# LB_BIT_o2_LONGLED-v02_rev1.net
KiCad netlist of a schematic drawn in EAGLE
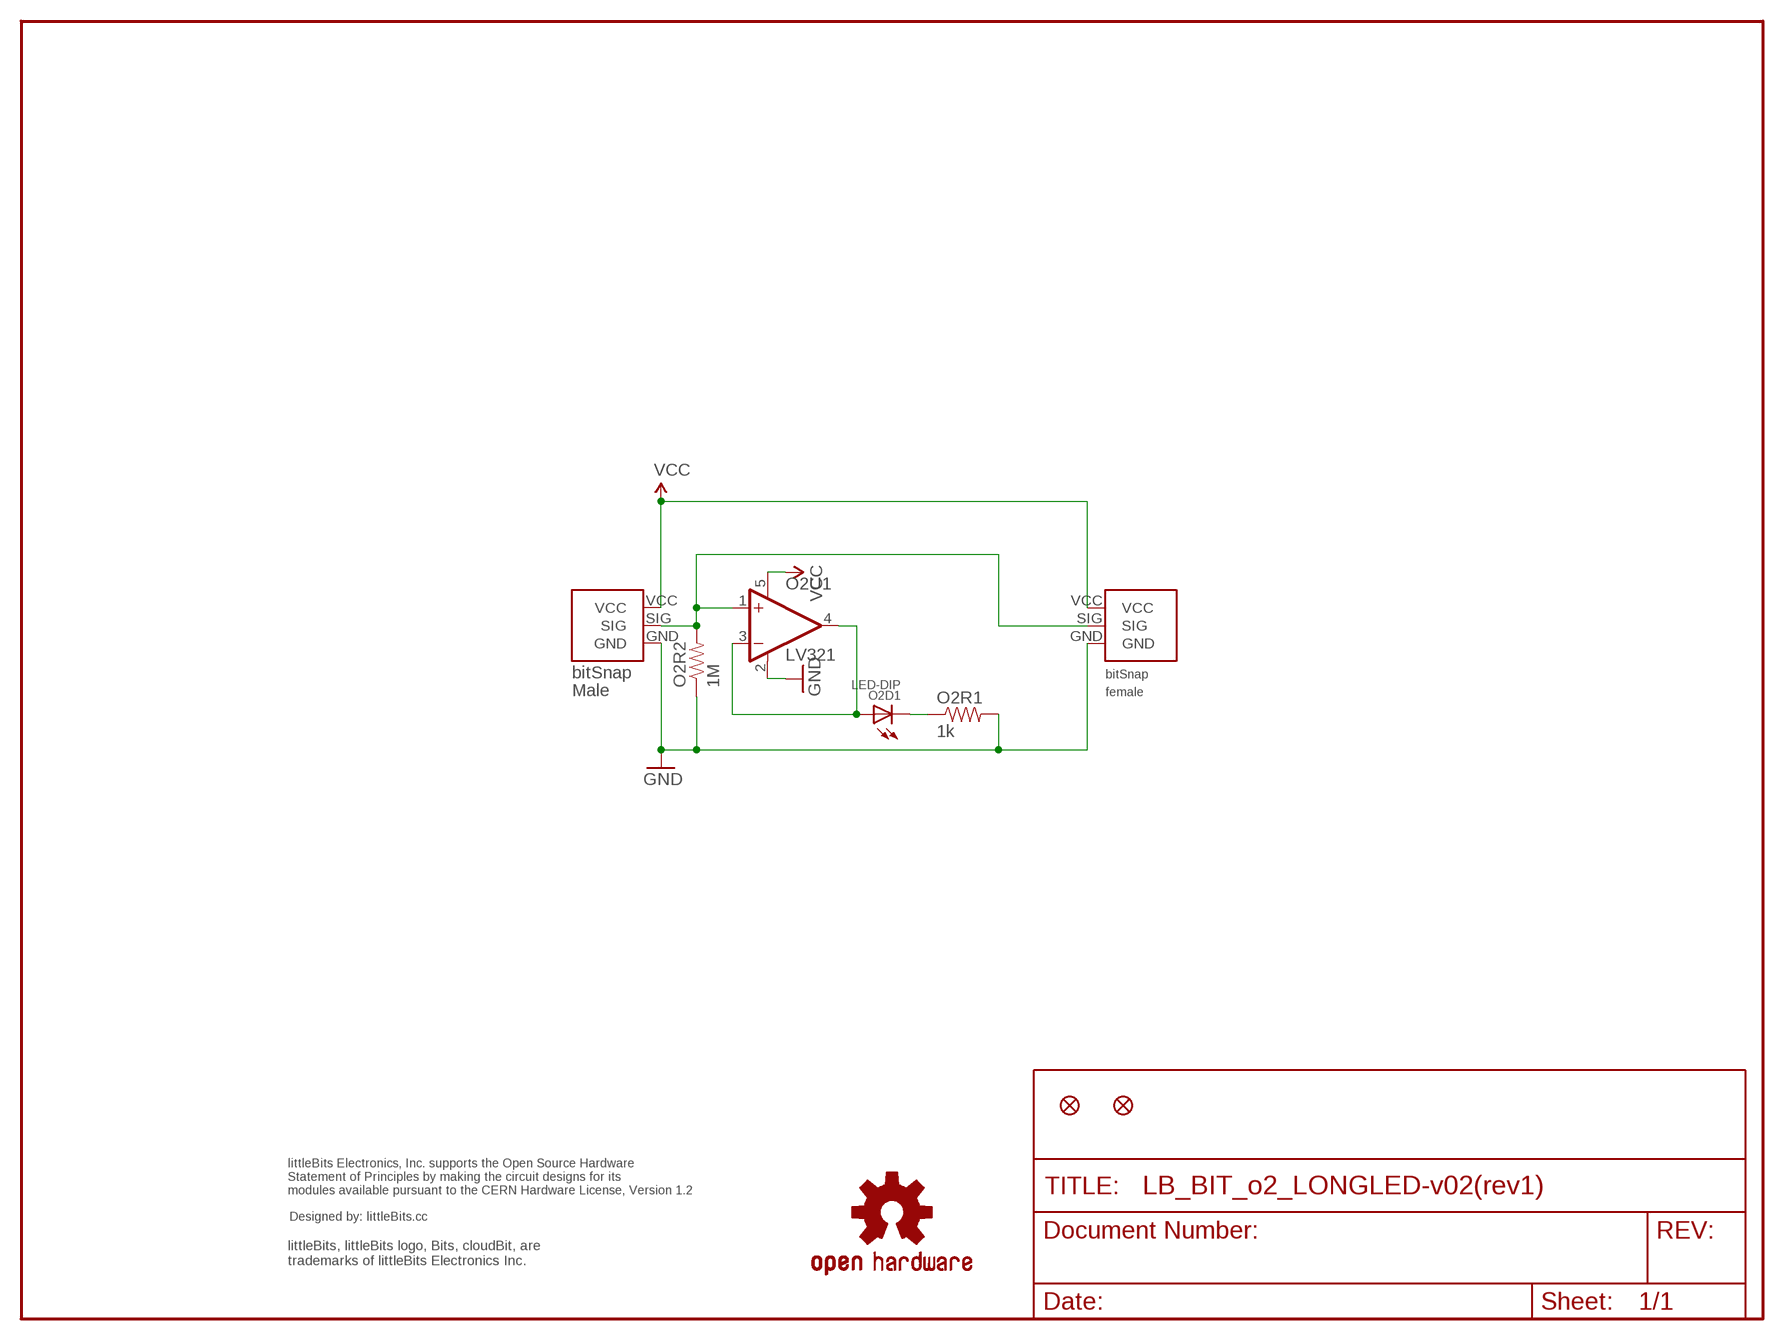
[diagram p0: schematic, sheet 1]

(export (version "E")
  (design (tool "Eeschema 10.0.6"))
  (components
    (comp (ref "O2BSF")
      (value "BITSNAP_FEMALE")
      (footprint "eagle-import:BITSNAP_FEMALE")
      (libsource (lib "eagle-import") (part "BITSNAP_FEMALE"))
    )
    (comp (ref "O2BSM")
      (value "BITSNAP_MALE")
      (footprint "eagle-import:BITSNAP_MALE")
      (libsource (lib "eagle-import") (part "BITSNAP_MALE"))
    )
    (comp (ref "O2D1")
      (value "LED-DIP")
      (footprint "eagle-import:LED-DIP")
      (libsource (lib "eagle-import") (part "LED-DIP"))
    )
    (comp (ref "O2FD1")
      (value "FIDUCIAL1X2")
      (footprint "eagle-import:FIDUCIAL-1X2")
      (libsource (lib "eagle-import") (part "FIDUCIAL1X2"))
    )
    (comp (ref "O2FD2")
      (value "FIDUCIAL1X2")
      (footprint "eagle-import:FIDUCIAL-1X2")
      (libsource (lib "eagle-import") (part "FIDUCIAL1X2"))
    )
    (comp (ref "O2R1")
      (value "1k")
      (footprint "eagle-import:0603-RES")
      (libsource (lib "eagle-import") (part "RESISTOR0603-RES"))
    )
    (comp (ref "O2R2")
      (value "1M")
      (footprint "eagle-import:0603-RES")
      (libsource (lib "eagle-import") (part "RESISTOR0603-RES"))
    )
    (comp (ref "O2U1")
      (value "LV321")
      (footprint "eagle-import:SC70-5")
      (libsource (lib "eagle-import") (part "LV321"))
    )
    (comp (ref "U$5")
      (value "OSHWCREDIT")
      (footprint "eagle-import:OSHWCREDIT")
      (libsource (lib "eagle-import") (part "OSHWCREDIT"))
    )
    (comp (ref "U$14")
      (value "OSHW-LOGOL")
      (footprint "eagle-import:OSHW-LOGO-L")
      (libsource (lib "eagle-import") (part "OSHW-LOGOL"))
    )
  )
  (nets
    (net (code "1") (name "GND") (class "Default")
      (node (ref "O2BSF") (pin "GND") (pinfunction "GND_GND") (pintype "bidirectional"))
      (node (ref "O2BSM") (pin "GND") (pinfunction "GND_GND") (pintype "bidirectional"))
      (node (ref "O2R1") (pin "2") (pinfunction "2_2") (pintype "passive"))
      (node (ref "O2R2") (pin "1") (pinfunction "1_1") (pintype "passive"))
      (node (ref "O2U1") (pin "2") (pinfunction "V-_2") (pintype "power_in"))
    )
    (net (code "2") (name "Net-(O2D1-PadC)") (class "Default")
      (node (ref "O2D1") (pin "C") (pinfunction "C_C") (pintype "passive"))
      (node (ref "O2R1") (pin "1") (pinfunction "1_1") (pintype "passive"))
    )
    (net (code "3") (name "Net-(O2U1-+IN)") (class "Default")
      (node (ref "O2BSF") (pin "SIG") (pinfunction "SIG_SIG") (pintype "bidirectional"))
      (node (ref "O2BSM") (pin "SIG") (pinfunction "SIG_SIG") (pintype "bidirectional"))
      (node (ref "O2R2") (pin "2") (pinfunction "2_2") (pintype "passive"))
      (node (ref "O2U1") (pin "1") (pinfunction "+IN_1") (pintype "input"))
    )
    (net (code "4") (name "Net-(O2U1--IN)") (class "Default")
      (node (ref "O2D1") (pin "A") (pinfunction "A_A") (pintype "passive"))
      (node (ref "O2U1") (pin "3") (pinfunction "-IN_3") (pintype "input"))
      (node (ref "O2U1") (pin "4") (pinfunction "OUT_4") (pintype "output"))
    )
    (net (code "5") (name "VCC") (class "Default")
      (node (ref "O2BSF") (pin "VCC") (pinfunction "VCC_VCC") (pintype "bidirectional"))
      (node (ref "O2BSM") (pin "VCC") (pinfunction "VCC_VCC") (pintype "bidirectional"))
      (node (ref "O2U1") (pin "5") (pinfunction "V+_5") (pintype "power_in"))
    )
  )
)
